# 1_Interface.net
KiCad netlist of a schematic drawn in Altium Designer
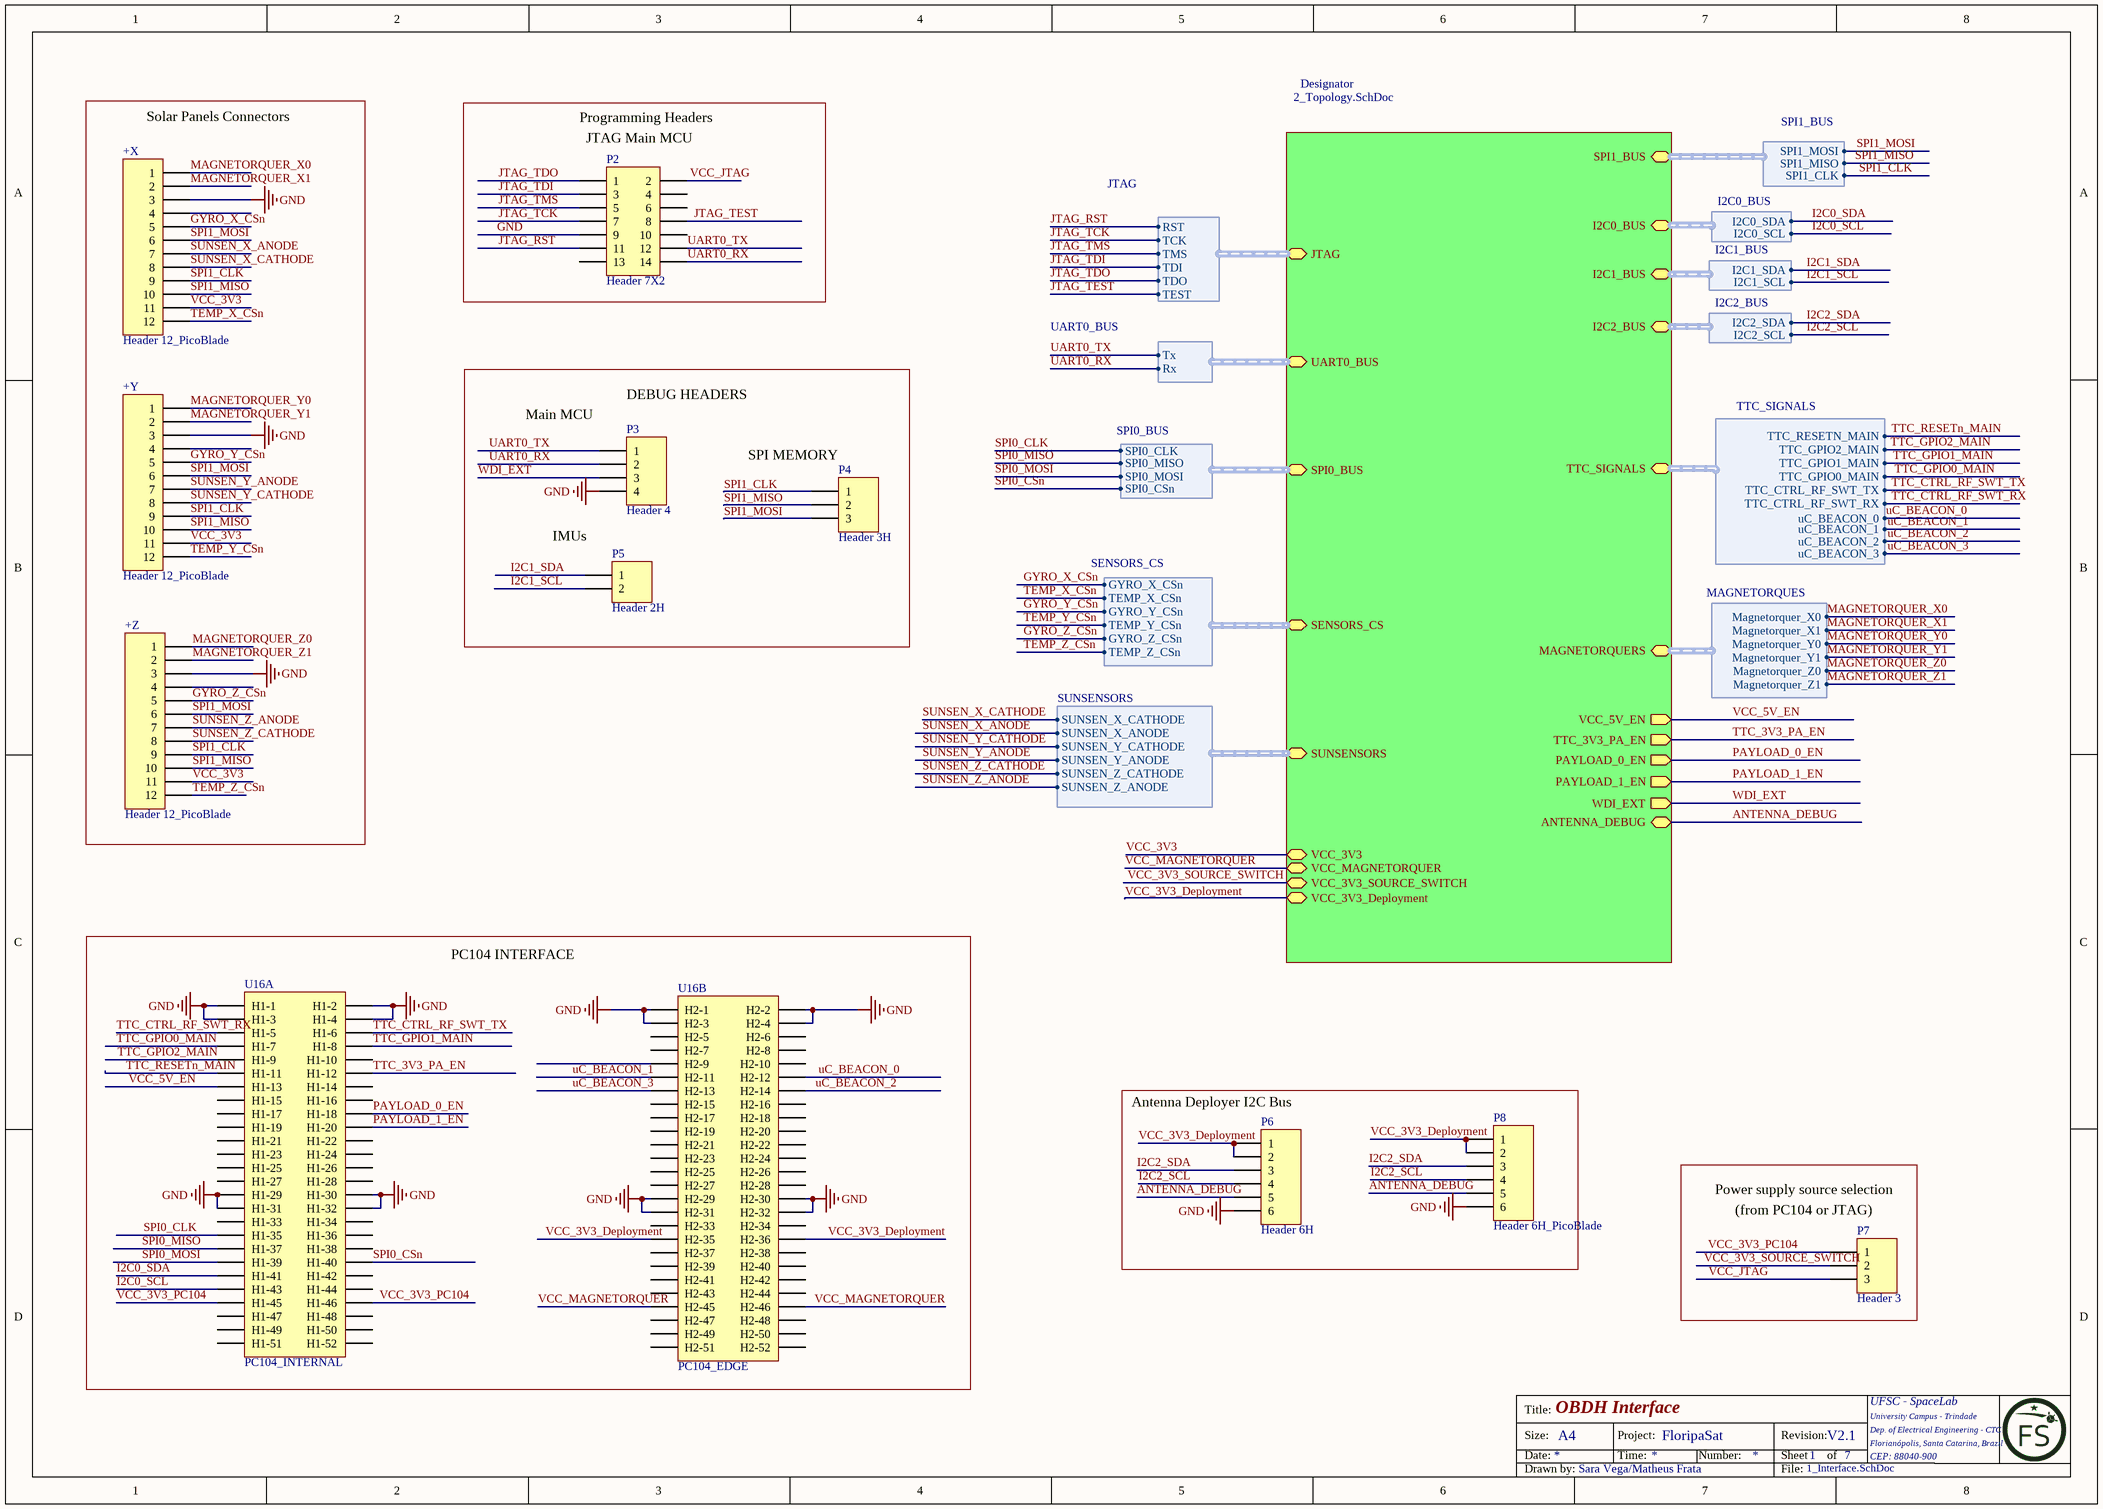
[diagram p0: 1_Interface.SchDoc]

(export (version "E")
  (design (tool "Eeschema 10.0.6"))
  (components
    (comp (ref "+X")
      (value "Header 12_PicoBlade")
      (footprint "HDR12 PicoBlade - duplicate")
      (description "Header, 12-Pin")
      (fields (field (name "PARTNUMBER") "53398-1271") (field (name "PUBLISHER") "Altium Limited"))
      (libsource (lib "FloripaSatSchlib") (part "Header 12_PicoBlade"))
    )
    (comp (ref "+Y")
      (value "Header 12_PicoBlade")
      (footprint "HDR12 PicoBlade - duplicate")
      (description "Header, 12-Pin")
      (fields (field (name "PARTNUMBER") "53398-1271") (field (name "PUBLISHER") "Altium Limited"))
      (libsource (lib "FloripaSatSchlib") (part "Header 12_PicoBlade"))
    )
    (comp (ref "+Z")
      (value "Header 12_PicoBlade")
      (footprint "HDR12 PicoBlade - duplicate")
      (description "Header, 12-Pin")
      (fields (field (name "PARTNUMBER") "533981271") (field (name "PUBLISHER") "Altium Limited"))
      (libsource (lib "FloripaSatSchlib") (part "Header 12_PicoBlade"))
    )
    (comp (ref "P2")
      (value "Header 7X2")
      (footprint "HDR2X7")
      (description "Header, 7-Pin, Dual row")
      (fields (field (name "PUBLISHER") "Altium Limited"))
      (libsource (lib "Miscellaneous Connectors") (part "Header 7X2"))
    )
    (comp (ref "P3")
      (value "Header 4")
      (footprint "HDR1X4")
      (description "Header, 4-Pin")
      (fields (field (name "PUBLISHER") "Altium Limited"))
      (libsource (lib "Miscellaneous Connectors") (part "Header 4"))
    )
    (comp (ref "P4")
      (value "Header 3H")
      (footprint "HDR 1X3")
      (description "Header, 3-Pin, Right Angle")
      (fields (field (name "PARTNUMBER") "4-103327-5") (field (name "PUBLISHER") "Altium Limited"))
      (libsource (lib "FloripaSatSchlib") (part "Header 3H"))
    )
    (comp (ref "P5")
      (value "Header 2H")
      (footprint "HDR1X2H")
      (description "Header, 2-Pin, Right Angle")
      (fields (field (name "PUBLISHER") "Altium Limited"))
      (libsource (lib "Miscellaneous Connectors") (part "Header 2H"))
    )
    (comp (ref "P6")
      (value "Header 6H")
      (footprint "HDR1X6H")
      (description "Header, 6-Pin, Right Angle")
      (fields (field (name "PUBLISHER") "Altium Limited"))
      (libsource (lib "Miscellaneous Connectors") (part "Header 6H"))
    )
    (comp (ref "P7")
      (value "Header 3")
      (footprint "HDR1X3")
      (description "Header, 3-Pin")
      (fields (field (name "PUBLISHER") "Altium Limited"))
      (libsource (lib "Miscellaneous Connectors") (part "Header 3"))
    )
    (comp (ref "P8")
      (value "Header 6H_PicoBlade")
      (footprint "HDR6 PicoBlade")
      (description "Header, 6-Pin, Right Angle")
      (fields (field (name "PARTNUMBER") "53398-0671") (field (name "PUBLISHER") "Altium Limited"))
      (libsource (lib "FloripaSatSchlib") (part "Header 6H_PicoBlade"))
    )
    (comp (ref "U16")
      (value "PC104_INTERNAL")
      (footprint "PC104")
      (description "PC104")
      (fields (field (name "PARTNUMBER") "ESQ-126-39-G-D"))
      (libsource (lib "") (part "PC104_1"))
    )
  )
  (nets
    (net (code "13") (name "/ANTENNA_DEBUG") (class "Default")
      (node (ref "P6") (pin "5") (pinfunction "5_5") (pintype "passive"))
      (node (ref "P8") (pin "5") (pinfunction "5_5") (pintype "passive"))
    )
    (net (code "14") (name "/GYRO_X_CSn") (class "Default")
      (node (ref "+X") (pin "5") (pinfunction "5_5") (pintype "passive"))
    )
    (net (code "15") (name "/GYRO_Y_CSn") (class "Default")
      (node (ref "+Y") (pin "5") (pinfunction "5_5") (pintype "passive"))
    )
    (net (code "16") (name "/GYRO_Z_CSn") (class "Default")
      (node (ref "+Z") (pin "5") (pinfunction "5_5") (pintype "passive"))
    )
    (net (code "17") (name "/I2C0_SCL") (class "Default")
      (node (ref "U16") (pin "H1-43") (pinfunction "H1-43_H1-43") (pintype "passive"))
    )
    (net (code "18") (name "/I2C0_SDA") (class "Default")
      (node (ref "U16") (pin "H1-41") (pinfunction "H1-41_H1-41") (pintype "passive"))
    )
    (net (code "19") (name "/I2C1_SCL") (class "Default")
      (node (ref "P5") (pin "2") (pinfunction "2_2") (pintype "passive"))
    )
    (net (code "20") (name "/I2C1_SDA") (class "Default")
      (node (ref "P5") (pin "1") (pinfunction "1_1") (pintype "passive"))
    )
    (net (code "21") (name "/I2C2_SCL") (class "Default")
      (node (ref "P6") (pin "4") (pinfunction "4_4") (pintype "passive"))
      (node (ref "P8") (pin "4") (pinfunction "4_4") (pintype "passive"))
    )
    (net (code "22") (name "/I2C2_SDA") (class "Default")
      (node (ref "P6") (pin "3") (pinfunction "3_3") (pintype "passive"))
      (node (ref "P8") (pin "3") (pinfunction "3_3") (pintype "passive"))
    )
    (net (code "23") (name "/JTAG_RST") (class "Default")
      (node (ref "P2") (pin "11") (pinfunction "11_11") (pintype "passive"))
    )
    (net (code "24") (name "/JTAG_TCK") (class "Default")
      (node (ref "P2") (pin "7") (pinfunction "7_7") (pintype "passive"))
    )
    (net (code "25") (name "/JTAG_TDI") (class "Default")
      (node (ref "P2") (pin "3") (pinfunction "3_3") (pintype "passive"))
    )
    (net (code "26") (name "/JTAG_TDO") (class "Default")
      (node (ref "P2") (pin "1") (pinfunction "1_1") (pintype "passive"))
    )
    (net (code "27") (name "/JTAG_TEST") (class "Default")
      (node (ref "P2") (pin "8") (pinfunction "8_8") (pintype "passive"))
    )
    (net (code "28") (name "/JTAG_TMS") (class "Default")
      (node (ref "P2") (pin "5") (pinfunction "5_5") (pintype "passive"))
    )
    (net (code "29") (name "/MAGNETORQUER_X0") (class "Default")
      (node (ref "+X") (pin "1") (pinfunction "1_1") (pintype "passive"))
    )
    (net (code "30") (name "/MAGNETORQUER_X1") (class "Default")
      (node (ref "+X") (pin "2") (pinfunction "2_2") (pintype "passive"))
    )
    (net (code "31") (name "/MAGNETORQUER_Y0") (class "Default")
      (node (ref "+Y") (pin "1") (pinfunction "1_1") (pintype "passive"))
    )
    (net (code "32") (name "/MAGNETORQUER_Y1") (class "Default")
      (node (ref "+Y") (pin "2") (pinfunction "2_2") (pintype "passive"))
    )
    (net (code "33") (name "/MAGNETORQUER_Z0") (class "Default")
      (node (ref "+Z") (pin "1") (pinfunction "1_1") (pintype "passive"))
    )
    (net (code "34") (name "/MAGNETORQUER_Z1") (class "Default")
      (node (ref "+Z") (pin "2") (pinfunction "2_2") (pintype "passive"))
    )
    (net (code "35") (name "/PAYLOAD_0_EN") (class "Default")
      (node (ref "U16") (pin "H1-18") (pinfunction "H1-18_H1-18") (pintype "passive"))
    )
    (net (code "36") (name "/PAYLOAD_1_EN") (class "Default")
      (node (ref "U16") (pin "H1-20") (pinfunction "H1-20_H1-20") (pintype "passive"))
    )
    (net (code "37") (name "/SPI0_CLK") (class "Default")
      (node (ref "U16") (pin "H1-35") (pinfunction "H1-35_H1-35") (pintype "passive"))
    )
    (net (code "38") (name "/SPI0_CSn") (class "Default")
      (node (ref "U16") (pin "H1-40") (pinfunction "H1-40_H1-40") (pintype "passive"))
    )
    (net (code "39") (name "/SPI0_MISO") (class "Default")
      (node (ref "U16") (pin "H1-37") (pinfunction "H1-37_H1-37") (pintype "passive"))
    )
    (net (code "40") (name "/SPI0_MOSI") (class "Default")
      (node (ref "U16") (pin "H1-39") (pinfunction "H1-39_H1-39") (pintype "passive"))
    )
    (net (code "41") (name "/SPI1_CLK") (class "Default")
      (node (ref "+X") (pin "9") (pinfunction "9_9") (pintype "passive"))
      (node (ref "+Y") (pin "9") (pinfunction "9_9") (pintype "passive"))
      (node (ref "+Z") (pin "9") (pinfunction "9_9") (pintype "passive"))
      (node (ref "P4") (pin "1") (pinfunction "1_1") (pintype "passive"))
    )
    (net (code "42") (name "/SPI1_MISO") (class "Default")
      (node (ref "+X") (pin "10") (pinfunction "10_10") (pintype "passive"))
      (node (ref "+Y") (pin "10") (pinfunction "10_10") (pintype "passive"))
      (node (ref "+Z") (pin "10") (pinfunction "10_10") (pintype "passive"))
      (node (ref "P4") (pin "2") (pinfunction "2_2") (pintype "passive"))
    )
    (net (code "43") (name "/SPI1_MOSI") (class "Default")
      (node (ref "+X") (pin "6") (pinfunction "6_6") (pintype "passive"))
      (node (ref "+Y") (pin "6") (pinfunction "6_6") (pintype "passive"))
      (node (ref "+Z") (pin "6") (pinfunction "6_6") (pintype "passive"))
      (node (ref "P4") (pin "3") (pinfunction "3_3") (pintype "passive"))
    )
    (net (code "44") (name "/SUNSEN_X_ANODE") (class "Default")
      (node (ref "+X") (pin "7") (pinfunction "7_7") (pintype "passive"))
    )
    (net (code "45") (name "/SUNSEN_X_CATHODE") (class "Default")
      (node (ref "+X") (pin "8") (pinfunction "8_8") (pintype "passive"))
    )
    (net (code "46") (name "/SUNSEN_Y_ANODE") (class "Default")
      (node (ref "+Y") (pin "7") (pinfunction "7_7") (pintype "passive"))
    )
    (net (code "47") (name "/SUNSEN_Y_CATHODE") (class "Default")
      (node (ref "+Y") (pin "8") (pinfunction "8_8") (pintype "passive"))
    )
    (net (code "48") (name "/SUNSEN_Z_ANODE") (class "Default")
      (node (ref "+Z") (pin "7") (pinfunction "7_7") (pintype "passive"))
    )
    (net (code "49") (name "/SUNSEN_Z_CATHODE") (class "Default")
      (node (ref "+Z") (pin "8") (pinfunction "8_8") (pintype "passive"))
    )
    (net (code "50") (name "/TEMP_X_CSn") (class "Default")
      (node (ref "+X") (pin "12") (pinfunction "12_12") (pintype "passive"))
    )
    (net (code "51") (name "/TEMP_Y_CSn") (class "Default")
      (node (ref "+Y") (pin "12") (pinfunction "12_12") (pintype "passive"))
    )
    (net (code "52") (name "/TEMP_Z_CSn") (class "Default")
      (node (ref "+Z") (pin "12") (pinfunction "12_12") (pintype "passive"))
    )
    (net (code "53") (name "/TTC_3V3_PA_EN") (class "Default")
      (node (ref "U16") (pin "H1-12") (pinfunction "H1-12_H1-12") (pintype "passive"))
    )
    (net (code "54") (name "/TTC_CTRL_RF_SWT_RX") (class "Default")
      (node (ref "U16") (pin "H1-5") (pinfunction "H1-5_H1-5") (pintype "passive"))
    )
    (net (code "55") (name "/TTC_CTRL_RF_SWT_TX") (class "Default")
      (node (ref "U16") (pin "H1-6") (pinfunction "H1-6_H1-6") (pintype "passive"))
    )
    (net (code "56") (name "/TTC_GPIO0_MAIN") (class "Default")
      (node (ref "U16") (pin "H1-7") (pinfunction "H1-7_H1-7") (pintype "passive"))
    )
    (net (code "57") (name "/TTC_GPIO1_MAIN") (class "Default")
      (node (ref "U16") (pin "H1-8") (pinfunction "H1-8_H1-8") (pintype "passive"))
    )
    (net (code "58") (name "/TTC_GPIO2_MAIN") (class "Default")
      (node (ref "U16") (pin "H1-9") (pinfunction "H1-9_H1-9") (pintype "passive"))
    )
    (net (code "59") (name "/TTC_RESETn_MAIN") (class "Default")
      (node (ref "U16") (pin "H1-11") (pinfunction "H1-11_H1-11") (pintype "passive"))
    )
    (net (code "60") (name "/UART0_RX") (class "Default")
      (node (ref "P2") (pin "14") (pinfunction "14_14") (pintype "passive"))
      (node (ref "P3") (pin "2") (pinfunction "2_2") (pintype "passive"))
    )
    (net (code "61") (name "/UART0_TX") (class "Default")
      (node (ref "P2") (pin "12") (pinfunction "12_12") (pintype "passive"))
      (node (ref "P3") (pin "1") (pinfunction "1_1") (pintype "passive"))
    )
    (net (code "62") (name "/VCC_3V3") (class "Default")
      (node (ref "+X") (pin "11") (pinfunction "11_11") (pintype "passive"))
      (node (ref "+Y") (pin "11") (pinfunction "11_11") (pintype "passive"))
      (node (ref "+Z") (pin "11") (pinfunction "11_11") (pintype "passive"))
    )
    (net (code "63") (name "/VCC_3V3_Deployment") (class "Default")
      (node (ref "P6") (pin "1") (pinfunction "1_1") (pintype "passive"))
      (node (ref "P6") (pin "2") (pinfunction "2_2") (pintype "passive"))
      (node (ref "P8") (pin "1") (pinfunction "1_1") (pintype "passive"))
      (node (ref "P8") (pin "2") (pinfunction "2_2") (pintype "passive"))
      (node (ref "U16") (pin "H2-35") (pinfunction "H2-35_H2-35") (pintype "passive"))
      (node (ref "U16") (pin "H2-36") (pinfunction "H2-36_H2-36") (pintype "passive"))
    )
    (net (code "64") (name "/VCC_3V3_PC104") (class "Default")
      (node (ref "P7") (pin "1") (pinfunction "1_1") (pintype "passive"))
      (node (ref "U16") (pin "H1-45") (pinfunction "H1-45_H1-45") (pintype "passive"))
      (node (ref "U16") (pin "H1-46") (pinfunction "H1-46_H1-46") (pintype "passive"))
    )
    (net (code "65") (name "/VCC_3V3_SOURCE_SWITCH") (class "Default")
      (node (ref "P7") (pin "2") (pinfunction "2_2") (pintype "passive"))
    )
    (net (code "66") (name "/VCC_5V_EN") (class "Default")
      (node (ref "U16") (pin "H1-13") (pinfunction "H1-13_H1-13") (pintype "passive"))
    )
    (net (code "67") (name "/VCC_JTAG") (class "Default")
      (node (ref "P2") (pin "2") (pinfunction "2_2") (pintype "passive"))
      (node (ref "P7") (pin "3") (pinfunction "3_3") (pintype "passive"))
    )
    (net (code "68") (name "/VCC_MAGNETORQUER") (class "Default")
      (node (ref "U16") (pin "H2-45") (pinfunction "H2-45_H2-45") (pintype "passive"))
      (node (ref "U16") (pin "H2-46") (pinfunction "H2-46_H2-46") (pintype "passive"))
    )
    (net (code "69") (name "/WDI_EXT") (class "Default")
      (node (ref "P3") (pin "3") (pinfunction "3_3") (pintype "passive"))
    )
    (net (code "70") (name "/uC_BEACON_0") (class "Default")
      (node (ref "U16") (pin "H2-12") (pinfunction "H2-12_H2-12") (pintype "passive"))
    )
    (net (code "71") (name "/uC_BEACON_1") (class "Default")
      (node (ref "U16") (pin "H2-11") (pinfunction "H2-11_H2-11") (pintype "passive"))
    )
    (net (code "72") (name "/uC_BEACON_2") (class "Default")
      (node (ref "U16") (pin "H2-14") (pinfunction "H2-14_H2-14") (pintype "passive"))
    )
    (net (code "73") (name "/uC_BEACON_3") (class "Default")
      (node (ref "U16") (pin "H2-13") (pinfunction "H2-13_H2-13") (pintype "passive"))
    )
    (net (code "85") (name "GND") (class "Default")
      (node (ref "+X") (pin "3") (pinfunction "3_3") (pintype "passive"))
      (node (ref "+Y") (pin "3") (pinfunction "3_3") (pintype "passive"))
      (node (ref "+Z") (pin "3") (pinfunction "3_3") (pintype "passive"))
      (node (ref "P2") (pin "9") (pinfunction "9_9") (pintype "passive"))
      (node (ref "P3") (pin "4") (pinfunction "4_4") (pintype "passive"))
      (node (ref "P6") (pin "6") (pinfunction "6_6") (pintype "passive"))
      (node (ref "P8") (pin "6") (pinfunction "6_6") (pintype "passive"))
      (node (ref "U16") (pin "H1-1") (pinfunction "H1-1_H1-1") (pintype "passive"))
      (node (ref "U16") (pin "H1-2") (pinfunction "H1-2_H1-2") (pintype "passive"))
      (node (ref "U16") (pin "H1-29") (pinfunction "H1-29_H1-29") (pintype "passive"))
      (node (ref "U16") (pin "H1-3") (pinfunction "H1-3_H1-3") (pintype "passive"))
      (node (ref "U16") (pin "H1-30") (pinfunction "H1-30_H1-30") (pintype "passive"))
      (node (ref "U16") (pin "H1-31") (pinfunction "H1-31_H1-31") (pintype "passive"))
      (node (ref "U16") (pin "H1-32") (pinfunction "H1-32_H1-32") (pintype "passive"))
      (node (ref "U16") (pin "H1-4") (pinfunction "H1-4_H1-4") (pintype "passive"))
      (node (ref "U16") (pin "H2-1") (pinfunction "H2-1_H2-1") (pintype "passive"))
      (node (ref "U16") (pin "H2-2") (pinfunction "H2-2_H2-2") (pintype "passive"))
      (node (ref "U16") (pin "H2-29") (pinfunction "H2-29_H2-29") (pintype "passive"))
      (node (ref "U16") (pin "H2-3") (pinfunction "H2-3_H2-3") (pintype "passive"))
      (node (ref "U16") (pin "H2-30") (pinfunction "H2-30_H2-30") (pintype "passive"))
      (node (ref "U16") (pin "H2-31") (pinfunction "H2-31_H2-31") (pintype "passive"))
      (node (ref "U16") (pin "H2-32") (pinfunction "H2-32_H2-32") (pintype "passive"))
      (node (ref "U16") (pin "H2-4") (pinfunction "H2-4_H2-4") (pintype "passive"))
    )
    (net (code "86") (name "unconnected-(+X-Pad4)") (class "Default")
      (node (ref "+X") (pin "4") (pinfunction "4_4") (pintype "passive"))
    )
    (net (code "87") (name "unconnected-(+Y-Pad4)") (class "Default")
      (node (ref "+Y") (pin "4") (pinfunction "4_4") (pintype "passive"))
    )
    (net (code "88") (name "unconnected-(+Z-Pad4)") (class "Default")
      (node (ref "+Z") (pin "4") (pinfunction "4_4") (pintype "passive"))
    )
    (net (code "89") (name "unconnected-(P2-Pad4)") (class "Default")
      (node (ref "P2") (pin "4") (pinfunction "4_4") (pintype "passive"))
    )
    (net (code "90") (name "unconnected-(P2-Pad6)") (class "Default")
      (node (ref "P2") (pin "6") (pinfunction "6_6") (pintype "passive"))
    )
    (net (code "91") (name "unconnected-(P2-Pad10)") (class "Default")
      (node (ref "P2") (pin "10") (pinfunction "10_10") (pintype "passive"))
    )
    (net (code "92") (name "unconnected-(P2-Pad13)") (class "Default")
      (node (ref "P2") (pin "13") (pinfunction "13_13") (pintype "passive"))
    )
    (net (code "93") (name "unconnected-(U16-PadH1-10)") (class "Default")
      (node (ref "U16") (pin "H1-10") (pinfunction "H1-10_H1-10") (pintype "passive"))
    )
    (net (code "94") (name "unconnected-(U16-PadH1-14)") (class "Default")
      (node (ref "U16") (pin "H1-14") (pinfunction "H1-14_H1-14") (pintype "passive"))
    )
    (net (code "95") (name "unconnected-(U16-PadH1-15)") (class "Default")
      (node (ref "U16") (pin "H1-15") (pinfunction "H1-15_H1-15") (pintype "passive"))
    )
    (net (code "96") (name "unconnected-(U16-PadH1-16)") (class "Default")
      (node (ref "U16") (pin "H1-16") (pinfunction "H1-16_H1-16") (pintype "passive"))
    )
    (net (code "97") (name "unconnected-(U16-PadH1-17)") (class "Default")
      (node (ref "U16") (pin "H1-17") (pinfunction "H1-17_H1-17") (pintype "passive"))
    )
    (net (code "98") (name "unconnected-(U16-PadH1-19)") (class "Default")
      (node (ref "U16") (pin "H1-19") (pinfunction "H1-19_H1-19") (pintype "passive"))
    )
    (net (code "99") (name "unconnected-(U16-PadH1-21)") (class "Default")
      (node (ref "U16") (pin "H1-21") (pinfunction "H1-21_H1-21") (pintype "passive"))
    )
    (net (code "100") (name "unconnected-(U16-PadH1-22)") (class "Default")
      (node (ref "U16") (pin "H1-22") (pinfunction "H1-22_H1-22") (pintype "passive"))
    )
    (net (code "101") (name "unconnected-(U16-PadH1-23)") (class "Default")
      (node (ref "U16") (pin "H1-23") (pinfunction "H1-23_H1-23") (pintype "passive"))
    )
    (net (code "102") (name "unconnected-(U16-PadH1-24)") (class "Default")
      (node (ref "U16") (pin "H1-24") (pinfunction "H1-24_H1-24") (pintype "passive"))
    )
    (net (code "103") (name "unconnected-(U16-PadH1-25)") (class "Default")
      (node (ref "U16") (pin "H1-25") (pinfunction "H1-25_H1-25") (pintype "passive"))
    )
    (net (code "104") (name "unconnected-(U16-PadH1-26)") (class "Default")
      (node (ref "U16") (pin "H1-26") (pinfunction "H1-26_H1-26") (pintype "passive"))
    )
    (net (code "105") (name "unconnected-(U16-PadH1-27)") (class "Default")
      (node (ref "U16") (pin "H1-27") (pinfunction "H1-27_H1-27") (pintype "passive"))
    )
    (net (code "106") (name "unconnected-(U16-PadH1-28)") (class "Default")
      (node (ref "U16") (pin "H1-28") (pinfunction "H1-28_H1-28") (pintype "passive"))
    )
    (net (code "107") (name "unconnected-(U16-PadH1-33)") (class "Default")
      (node (ref "U16") (pin "H1-33") (pinfunction "H1-33_H1-33") (pintype "passive"))
    )
    (net (code "108") (name "unconnected-(U16-PadH1-34)") (class "Default")
      (node (ref "U16") (pin "H1-34") (pinfunction "H1-34_H1-34") (pintype "passive"))
    )
    (net (code "109") (name "unconnected-(U16-PadH1-36)") (class "Default")
      (node (ref "U16") (pin "H1-36") (pinfunction "H1-36_H1-36") (pintype "passive"))
    )
    (net (code "110") (name "unconnected-(U16-PadH1-38)") (class "Default")
      (node (ref "U16") (pin "H1-38") (pinfunction "H1-38_H1-38") (pintype "passive"))
    )
    (net (code "111") (name "unconnected-(U16-PadH1-42)") (class "Default")
      (node (ref "U16") (pin "H1-42") (pinfunction "H1-42_H1-42") (pintype "passive"))
    )
    (net (code "112") (name "unconnected-(U16-PadH1-44)") (class "Default")
      (node (ref "U16") (pin "H1-44") (pinfunction "H1-44_H1-44") (pintype "passive"))
    )
    (net (code "113") (name "unconnected-(U16-PadH1-47)") (class "Default")
      (node (ref "U16") (pin "H1-47") (pinfunction "H1-47_H1-47") (pintype "passive"))
    )
    (net (code "114") (name "unconnected-(U16-PadH1-48)") (class "Default")
      (node (ref "U16") (pin "H1-48") (pinfunction "H1-48_H1-48") (pintype "passive"))
    )
    (net (code "115") (name "unconnected-(U16-PadH1-49)") (class "Default")
      (node (ref "U16") (pin "H1-49") (pinfunction "H1-49_H1-49") (pintype "passive"))
    )
    (net (code "116") (name "unconnected-(U16-PadH1-50)") (class "Default")
      (node (ref "U16") (pin "H1-50") (pinfunction "H1-50_H1-50") (pintype "passive"))
    )
    (net (code "117") (name "unconnected-(U16-PadH1-51)") (class "Default")
      (node (ref "U16") (pin "H1-51") (pinfunction "H1-51_H1-51") (pintype "passive"))
    )
    (net (code "118") (name "unconnected-(U16-PadH1-52)") (class "Default")
      (node (ref "U16") (pin "H1-52") (pinfunction "H1-52_H1-52") (pintype "passive"))
    )
    (net (code "119") (name "unconnected-(U16-PadH2-5)") (class "Default")
      (node (ref "U16") (pin "H2-5") (pinfunction "H2-5_H2-5") (pintype "passive"))
    )
    (net (code "120") (name "unconnected-(U16-PadH2-6)") (class "Default")
      (node (ref "U16") (pin "H2-6") (pinfunction "H2-6_H2-6") (pintype "passive"))
    )
    (net (code "121") (name "unconnected-(U16-PadH2-7)") (class "Default")
      (node (ref "U16") (pin "H2-7") (pinfunction "H2-7_H2-7") (pintype "passive"))
    )
    (net (code "122") (name "unconnected-(U16-PadH2-8)") (class "Default")
      (node (ref "U16") (pin "H2-8") (pinfunction "H2-8_H2-8") (pintype "passive"))
    )
    (net (code "123") (name "unconnected-(U16-PadH2-9)") (class "Default")
      (node (ref "U16") (pin "H2-9") (pinfunction "H2-9_H2-9") (pintype "passive"))
    )
    (net (code "124") (name "unconnected-(U16-PadH2-10)") (class "Default")
      (node (ref "U16") (pin "H2-10") (pinfunction "H2-10_H2-10") (pintype "passive"))
    )
    (net (code "125") (name "unconnected-(U16-PadH2-15)") (class "Default")
      (node (ref "U16") (pin "H2-15") (pinfunction "H2-15_H2-15") (pintype "passive"))
    )
    (net (code "126") (name "unconnected-(U16-PadH2-16)") (class "Default")
      (node (ref "U16") (pin "H2-16") (pinfunction "H2-16_H2-16") (pintype "passive"))
    )
    (net (code "127") (name "unconnected-(U16-PadH2-17)") (class "Default")
      (node (ref "U16") (pin "H2-17") (pinfunction "H2-17_H2-17") (pintype "passive"))
    )
    (net (code "128") (name "unconnected-(U16-PadH2-18)") (class "Default")
      (node (ref "U16") (pin "H2-18") (pinfunction "H2-18_H2-18") (pintype "passive"))
    )
    (net (code "129") (name "unconnected-(U16-PadH2-19)") (class "Default")
      (node (ref "U16") (pin "H2-19") (pinfunction "H2-19_H2-19") (pintype "passive"))
    )
    (net (code "130") (name "unconnected-(U16-PadH2-20)") (class "Default")
      (node (ref "U16") (pin "H2-20") (pinfunction "H2-20_H2-20") (pintype "passive"))
    )
    (net (code "131") (name "unconnected-(U16-PadH2-21)") (class "Default")
      (node (ref "U16") (pin "H2-21") (pinfunction "H2-21_H2-21") (pintype "passive"))
    )
    (net (code "132") (name "unconnected-(U16-PadH2-22)") (class "Default")
      (node (ref "U16") (pin "H2-22") (pinfunction "H2-22_H2-22") (pintype "passive"))
    )
    (net (code "133") (name "unconnected-(U16-PadH2-23)") (class "Default")
      (node (ref "U16") (pin "H2-23") (pinfunction "H2-23_H2-23") (pintype "passive"))
    )
    (net (code "134") (name "unconnected-(U16-PadH2-24)") (class "Default")
      (node (ref "U16") (pin "H2-24") (pinfunction "H2-24_H2-24") (pintype "passive"))
    )
    (net (code "135") (name "unconnected-(U16-PadH2-25)") (class "Default")
      (node (ref "U16") (pin "H2-25") (pinfunction "H2-25_H2-25") (pintype "passive"))
    )
    (net (code "136") (name "unconnected-(U16-PadH2-26)") (class "Default")
      (node (ref "U16") (pin "H2-26") (pinfunction "H2-26_H2-26") (pintype "passive"))
    )
    (net (code "137") (name "unconnected-(U16-PadH2-27)") (class "Default")
      (node (ref "U16") (pin "H2-27") (pinfunction "H2-27_H2-27") (pintype "passive"))
    )
    (net (code "138") (name "unconnected-(U16-PadH2-28)") (class "Default")
      (node (ref "U16") (pin "H2-28") (pinfunction "H2-28_H2-28") (pintype "passive"))
    )
    (net (code "139") (name "unconnected-(U16-PadH2-33)") (class "Default")
      (node (ref "U16") (pin "H2-33") (pinfunction "H2-33_H2-33") (pintype "passive"))
    )
    (net (code "140") (name "unconnected-(U16-PadH2-34)") (class "Default")
      (node (ref "U16") (pin "H2-34") (pinfunction "H2-34_H2-34") (pintype "passive"))
    )
    (net (code "141") (name "unconnected-(U16-PadH2-37)") (class "Default")
      (node (ref "U16") (pin "H2-37") (pinfunction "H2-37_H2-37") (pintype "passive"))
    )
    (net (code "142") (name "unconnected-(U16-PadH2-38)") (class "Default")
      (node (ref "U16") (pin "H2-38") (pinfunction "H2-38_H2-38") (pintype "passive"))
    )
    (net (code "143") (name "unconnected-(U16-PadH2-39)") (class "Default")
      (node (ref "U16") (pin "H2-39") (pinfunction "H2-39_H2-39") (pintype "passive"))
    )
    (net (code "144") (name "unconnected-(U16-PadH2-40)") (class "Default")
      (node (ref "U16") (pin "H2-40") (pinfunction "H2-40_H2-40") (pintype "passive"))
    )
    (net (code "145") (name "unconnected-(U16-PadH2-41)") (class "Default")
      (node (ref "U16") (pin "H2-41") (pinfunction "H2-41_H2-41") (pintype "passive"))
    )
    (net (code "146") (name "unconnected-(U16-PadH2-42)") (class "Default")
      (node (ref "U16") (pin "H2-42") (pinfunction "H2-42_H2-42") (pintype "passive"))
    )
    (net (code "147") (name "unconnected-(U16-PadH2-43)") (class "Default")
      (node (ref "U16") (pin "H2-43") (pinfunction "H2-43_H2-43") (pintype "passive"))
    )
    (net (code "148") (name "unconnected-(U16-PadH2-44)") (class "Default")
      (node (ref "U16") (pin "H2-44") (pinfunction "H2-44_H2-44") (pintype "passive"))
    )
    (net (code "149") (name "unconnected-(U16-PadH2-47)") (class "Default")
      (node (ref "U16") (pin "H2-47") (pinfunction "H2-47_H2-47") (pintype "passive"))
    )
    (net (code "150") (name "unconnected-(U16-PadH2-48)") (class "Default")
      (node (ref "U16") (pin "H2-48") (pinfunction "H2-48_H2-48") (pintype "passive"))
    )
    (net (code "151") (name "unconnected-(U16-PadH2-49)") (class "Default")
      (node (ref "U16") (pin "H2-49") (pinfunction "H2-49_H2-49") (pintype "passive"))
    )
    (net (code "152") (name "unconnected-(U16-PadH2-50)") (class "Default")
      (node (ref "U16") (pin "H2-50") (pinfunction "H2-50_H2-50") (pintype "passive"))
    )
    (net (code "153") (name "unconnected-(U16-PadH2-51)") (class "Default")
      (node (ref "U16") (pin "H2-51") (pinfunction "H2-51_H2-51") (pintype "passive"))
    )
    (net (code "154") (name "unconnected-(U16-PadH2-52)") (class "Default")
      (node (ref "U16") (pin "H2-52") (pinfunction "H2-52_H2-52") (pintype "passive"))
    )
  )
)
